# Felderblock_mini.net
KiCad netlist of a schematic drawn in EAGLE
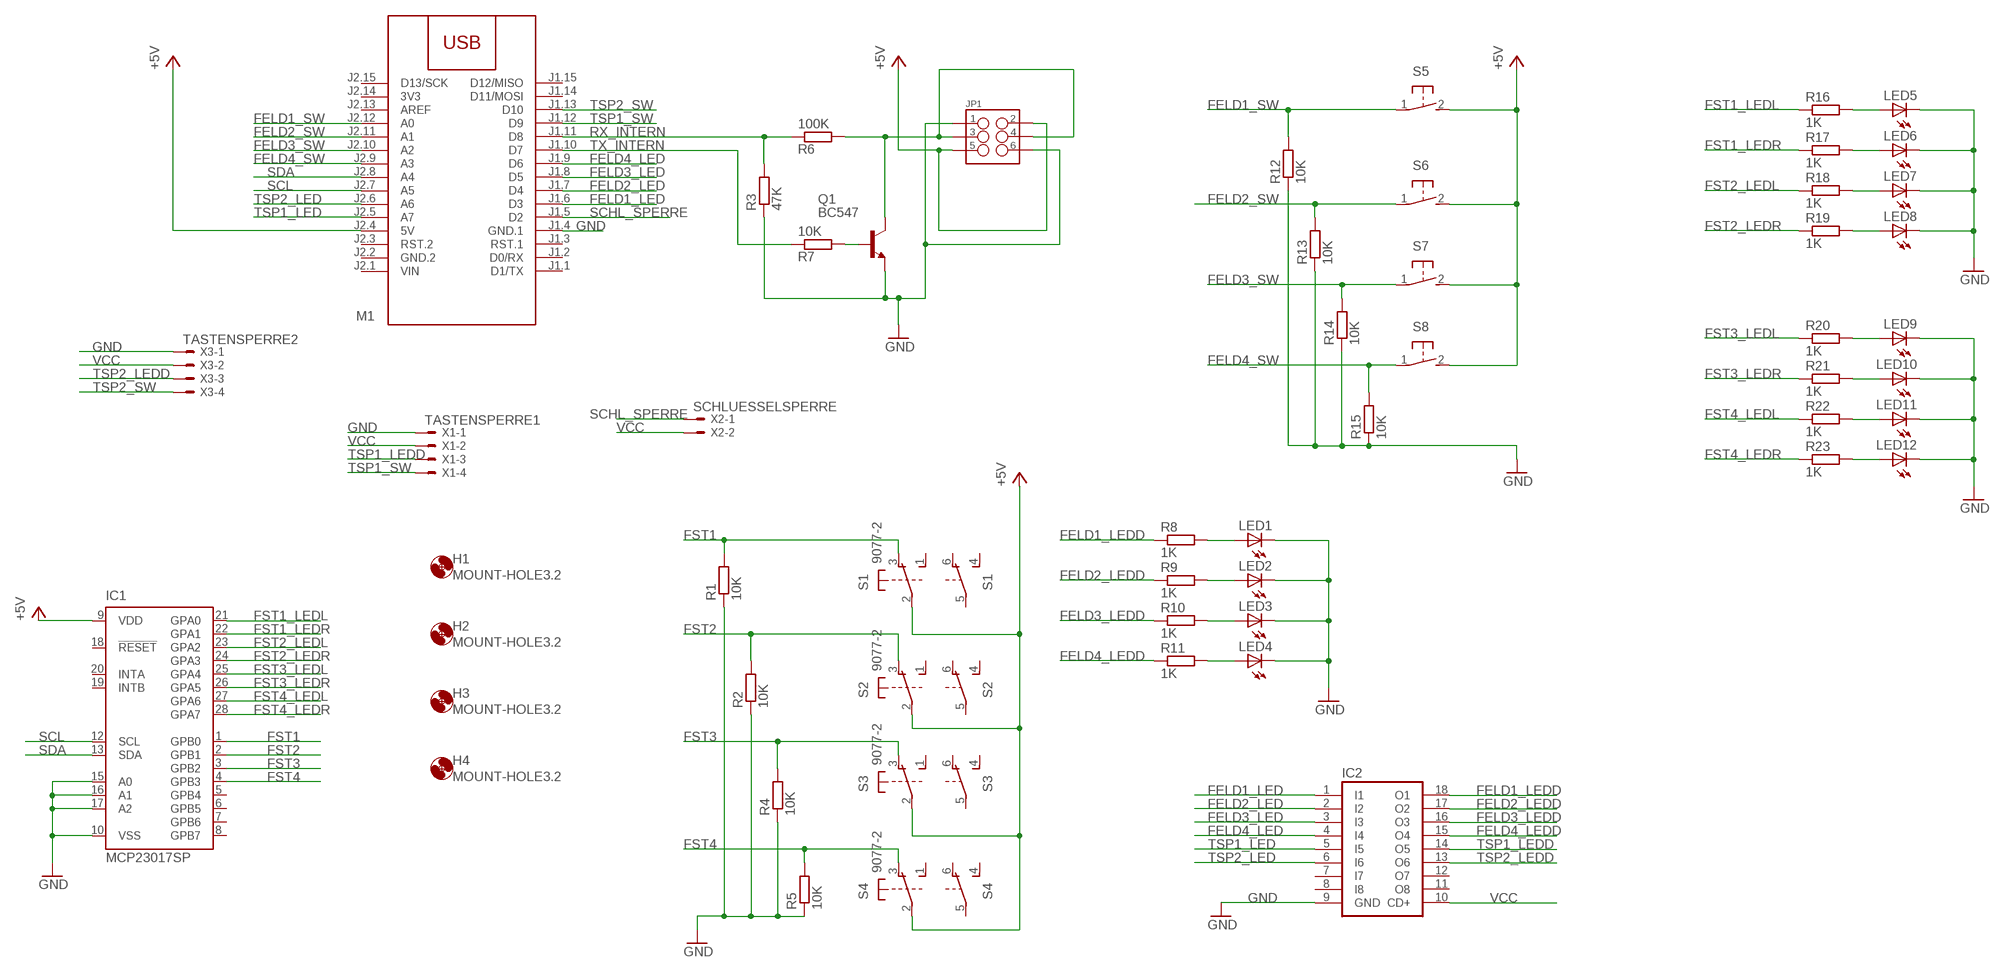
[diagram p0: schematic, sheet 1]

(export (version "E")
  (design (tool "Eeschema 10.0.6"))
  (components
    (comp (ref "H1")
      (value "MOUNT-HOLE3.2")
      (footprint "eagle-import:3,2")
      (libsource (lib "eagle-import") (part "MOUNT-HOLE3.2"))
    )
    (comp (ref "H2")
      (value "MOUNT-HOLE3.2")
      (footprint "eagle-import:3,2")
      (libsource (lib "eagle-import") (part "MOUNT-HOLE3.2"))
    )
    (comp (ref "H3")
      (value "MOUNT-HOLE3.2")
      (footprint "eagle-import:3,2")
      (libsource (lib "eagle-import") (part "MOUNT-HOLE3.2"))
    )
    (comp (ref "H4")
      (value "MOUNT-HOLE3.2")
      (footprint "eagle-import:3,2")
      (libsource (lib "eagle-import") (part "MOUNT-HOLE3.2"))
    )
    (comp (ref "IC1")
      (value "MCP23017SP")
      (footprint "eagle-import:DIL28-3")
      (fields (field (name "MF") "MICROCHIP") (field (name "MPN") "MCP23017-E/SP"))
      (libsource (lib "eagle-import") (part "MCP23017SP"))
    )
    (comp (ref "IC2")
      (value "ULN2803A")
      (footprint "eagle-import:DIL18")
      (libsource (lib "eagle-import") (part "ULN2803A"))
    )
    (comp (ref "JP1")
      (value "M03X2SHROUD")
      (footprint "eagle-import:2X3-SHROUDED")
      (libsource (lib "eagle-import") (part "M03X2SHROUD"))
    )
    (comp (ref "LED1")
      (value "LED10MM")
      (footprint "eagle-import:LED10MM")
      (libsource (lib "eagle-import") (part "LED10MM"))
    )
    (comp (ref "LED2")
      (value "LED10MM")
      (footprint "eagle-import:LED10MM")
      (libsource (lib "eagle-import") (part "LED10MM"))
    )
    (comp (ref "LED3")
      (value "LED10MM")
      (footprint "eagle-import:LED10MM")
      (libsource (lib "eagle-import") (part "LED10MM"))
    )
    (comp (ref "LED4")
      (value "LED10MM")
      (footprint "eagle-import:LED10MM")
      (libsource (lib "eagle-import") (part "LED10MM"))
    )
    (comp (ref "LED5")
      (value "LED5MM")
      (footprint "eagle-import:LED5MM")
      (libsource (lib "eagle-import") (part "LED5MM"))
    )
    (comp (ref "LED6")
      (value "LED5MM")
      (footprint "eagle-import:LED5MM")
      (libsource (lib "eagle-import") (part "LED5MM"))
    )
    (comp (ref "LED7")
      (value "LED5MM")
      (footprint "eagle-import:LED5MM")
      (libsource (lib "eagle-import") (part "LED5MM"))
    )
    (comp (ref "LED8")
      (value "LED5MM")
      (footprint "eagle-import:LED5MM")
      (libsource (lib "eagle-import") (part "LED5MM"))
    )
    (comp (ref "LED9")
      (value "LED5MM")
      (footprint "eagle-import:LED5MM")
      (libsource (lib "eagle-import") (part "LED5MM"))
    )
    (comp (ref "LED10")
      (value "LED5MM")
      (footprint "eagle-import:LED5MM")
      (libsource (lib "eagle-import") (part "LED5MM"))
    )
    (comp (ref "LED11")
      (value "LED5MM")
      (footprint "eagle-import:LED5MM")
      (libsource (lib "eagle-import") (part "LED5MM"))
    )
    (comp (ref "LED12")
      (value "LED5MM")
      (footprint "eagle-import:LED5MM")
      (libsource (lib "eagle-import") (part "LED5MM"))
    )
    (comp (ref "M1")
      (value "ARDUINO-NANO-3.0")
      (footprint "eagle-import:ARDUINO-NANO-3.0")
      (libsource (lib "eagle-import") (part "ARDUINO-NANO-3.0"))
    )
    (comp (ref "Q1")
      (value "BC547")
      (footprint "eagle-import:TO92")
      (libsource (lib "eagle-import") (part "BC547"))
    )
    (comp (ref "R1")
      (value "10K")
      (footprint "eagle-import:0207_7")
      (libsource (lib "eagle-import") (part "resistor_R-EU_0207/7"))
    )
    (comp (ref "R2")
      (value "10K")
      (footprint "eagle-import:0207_7")
      (libsource (lib "eagle-import") (part "resistor_R-EU_0207/7"))
    )
    (comp (ref "R3")
      (value "47K")
      (footprint "eagle-import:R1206")
      (libsource (lib "eagle-import") (part "R-EU_R1206"))
    )
    (comp (ref "R4")
      (value "10K")
      (footprint "eagle-import:0207_7")
      (libsource (lib "eagle-import") (part "resistor_R-EU_0207/7"))
    )
    (comp (ref "R5")
      (value "10K")
      (footprint "eagle-import:0207_7")
      (libsource (lib "eagle-import") (part "resistor_R-EU_0207/7"))
    )
    (comp (ref "R6")
      (value "100K")
      (footprint "eagle-import:R1206")
      (libsource (lib "eagle-import") (part "R-EU_R1206"))
    )
    (comp (ref "R7")
      (value "10K")
      (footprint "eagle-import:R1206")
      (libsource (lib "eagle-import") (part "R-EU_R1206"))
    )
    (comp (ref "R8")
      (value "1K")
      (footprint "eagle-import:0207_7")
      (libsource (lib "eagle-import") (part "resistor_R-EU_0207/7"))
    )
    (comp (ref "R9")
      (value "1K")
      (footprint "eagle-import:0207_7")
      (libsource (lib "eagle-import") (part "resistor_R-EU_0207/7"))
    )
    (comp (ref "R10")
      (value "1K")
      (footprint "eagle-import:0207_7")
      (libsource (lib "eagle-import") (part "resistor_R-EU_0207/7"))
    )
    (comp (ref "R11")
      (value "1K")
      (footprint "eagle-import:0207_7")
      (libsource (lib "eagle-import") (part "resistor_R-EU_0207/7"))
    )
    (comp (ref "R12")
      (value "10K")
      (footprint "eagle-import:0207_7")
      (libsource (lib "eagle-import") (part "resistor_R-EU_0207/7"))
    )
    (comp (ref "R13")
      (value "10K")
      (footprint "eagle-import:0207_7")
      (libsource (lib "eagle-import") (part "resistor_R-EU_0207/7"))
    )
    (comp (ref "R14")
      (value "10K")
      (footprint "eagle-import:0207_7")
      (libsource (lib "eagle-import") (part "resistor_R-EU_0207/7"))
    )
    (comp (ref "R15")
      (value "10K")
      (footprint "eagle-import:0207_7")
      (libsource (lib "eagle-import") (part "resistor_R-EU_0207/7"))
    )
    (comp (ref "R16")
      (value "1K")
      (footprint "eagle-import:0207_7")
      (libsource (lib "eagle-import") (part "resistor_R-EU_0207/7"))
    )
    (comp (ref "R17")
      (value "1K")
      (footprint "eagle-import:0207_7")
      (libsource (lib "eagle-import") (part "resistor_R-EU_0207/7"))
    )
    (comp (ref "R18")
      (value "1K")
      (footprint "eagle-import:0207_7")
      (libsource (lib "eagle-import") (part "resistor_R-EU_0207/7"))
    )
    (comp (ref "R19")
      (value "1K")
      (footprint "eagle-import:0207_7")
      (libsource (lib "eagle-import") (part "resistor_R-EU_0207/7"))
    )
    (comp (ref "R20")
      (value "1K")
      (footprint "eagle-import:0207_7")
      (libsource (lib "eagle-import") (part "resistor_R-EU_0207/7"))
    )
    (comp (ref "R21")
      (value "1K")
      (footprint "eagle-import:0207_7")
      (libsource (lib "eagle-import") (part "resistor_R-EU_0207/7"))
    )
    (comp (ref "R22")
      (value "1K")
      (footprint "eagle-import:0207_7")
      (libsource (lib "eagle-import") (part "resistor_R-EU_0207/7"))
    )
    (comp (ref "R23")
      (value "1K")
      (footprint "eagle-import:0207_7")
      (libsource (lib "eagle-import") (part "resistor_R-EU_0207/7"))
    )
    (comp (ref "S1")
      (value "9077-2")
      (footprint "eagle-import:9077-2")
      (libsource (lib "eagle-import") (part "9077-2"))
    )
    (comp (ref "S2")
      (value "9077-2")
      (footprint "eagle-import:9077-2")
      (libsource (lib "eagle-import") (part "9077-2"))
    )
    (comp (ref "S3")
      (value "9077-2")
      (footprint "eagle-import:9077-2")
      (libsource (lib "eagle-import") (part "9077-2"))
    )
    (comp (ref "S4")
      (value "9077-2")
      (footprint "eagle-import:9077-2")
      (libsource (lib "eagle-import") (part "9077-2"))
    )
    (comp (ref "S5")
      (value "31-XX")
      (footprint "eagle-import:B3F-31XX")
      (fields (field (name "MPN") "B3F-3100"))
      (libsource (lib "eagle-import") (part "31-XX"))
    )
    (comp (ref "S6")
      (value "31-XX")
      (footprint "eagle-import:B3F-31XX")
      (fields (field (name "MPN") "B3F-3100"))
      (libsource (lib "eagle-import") (part "31-XX"))
    )
    (comp (ref "S7")
      (value "31-XX")
      (footprint "eagle-import:B3F-31XX")
      (fields (field (name "MPN") "B3F-3100"))
      (libsource (lib "eagle-import") (part "31-XX"))
    )
    (comp (ref "S8")
      (value "31-XX")
      (footprint "eagle-import:B3F-31XX")
      (fields (field (name "MPN") "B3F-3100"))
      (libsource (lib "eagle-import") (part "31-XX"))
    )
    (comp (ref "X1")
      (value "TASTENSPERRE1")
      (footprint "eagle-import:22-23-2041")
      (fields (field (name "MF") "MOLEX") (field (name "MPN") "22-23-2041"))
      (libsource (lib "eagle-import") (part "22-23-2041"))
    )
    (comp (ref "X2")
      (value "SCHLUESSELSPERRE")
      (footprint "eagle-import:22-23-2021")
      (fields (field (name "MF") "MOLEX") (field (name "MPN") "22-23-2021"))
      (libsource (lib "eagle-import") (part "22-23-2021"))
    )
    (comp (ref "X3")
      (value "TASTENSPERRE2")
      (footprint "eagle-import:22-23-2041")
      (fields (field (name "MF") "MOLEX") (field (name "MPN") "22-23-2041"))
      (libsource (lib "eagle-import") (part "22-23-2041"))
    )
  )
  (nets
    (net (code "1") (name "+5V") (class "Default")
      (node (ref "IC1") (pin "9") (pinfunction "VDD_9") (pintype "power_in"))
      (node (ref "IC2") (pin "10") (pinfunction "CD+_10") (pintype "passive"))
      (node (ref "JP1") (pin "2") (pinfunction "2_2") (pintype "bidirectional"))
      (node (ref "JP1") (pin "5") (pinfunction "5_5") (pintype "bidirectional"))
      (node (ref "M1") (pin "J2.4") (pinfunction "5V_J2.4") (pintype "power_in"))
      (node (ref "S1") (pin "2") (pinfunction "P_2") (pintype "passive"))
      (node (ref "S2") (pin "2") (pinfunction "P_2") (pintype "passive"))
      (node (ref "S3") (pin "2") (pinfunction "P_2") (pintype "passive"))
      (node (ref "S4") (pin "2") (pinfunction "P_2") (pintype "passive"))
      (node (ref "S5") (pin "2") (pinfunction "S_2") (pintype "passive"))
      (node (ref "S6") (pin "2") (pinfunction "S_2") (pintype "passive"))
      (node (ref "S7") (pin "2") (pinfunction "S_2") (pintype "passive"))
      (node (ref "S8") (pin "2") (pinfunction "S_2") (pintype "passive"))
      (node (ref "X1") (pin "2") (pinfunction "S_2") (pintype "passive"))
      (node (ref "X2") (pin "2") (pinfunction "S_2") (pintype "passive"))
      (node (ref "X3") (pin "2") (pinfunction "S_2") (pintype "passive"))
    )
    (net (code "2") (name "/3V3") (class "Default")
      (node (ref "M1") (pin "J2.14") (pinfunction "3V3_J2.14") (pintype "power_in"))
    )
    (net (code "3") (name "/FELD1_LED") (class "Default")
      (node (ref "IC2") (pin "1") (pinfunction "I1_1") (pintype "input"))
      (node (ref "M1") (pin "J1.6") (pinfunction "D3_J1.6") (pintype "bidirectional"))
    )
    (net (code "4") (name "/FELD1_LEDD") (class "Default")
      (node (ref "IC2") (pin "18") (pinfunction "O1_18") (pintype "open_collector"))
      (node (ref "R8") (pin "1") (pinfunction "1_1") (pintype "passive"))
    )
    (net (code "5") (name "/FELD1_SW") (class "Default")
      (node (ref "M1") (pin "J2.12") (pinfunction "A0_J2.12") (pintype "bidirectional"))
      (node (ref "R12") (pin "2") (pinfunction "2_2") (pintype "passive"))
      (node (ref "S5") (pin "1") (pinfunction "P_1") (pintype "passive"))
    )
    (net (code "6") (name "/FELD2_LED") (class "Default")
      (node (ref "IC2") (pin "2") (pinfunction "I2_2") (pintype "input"))
      (node (ref "M1") (pin "J1.7") (pinfunction "D4_J1.7") (pintype "bidirectional"))
    )
    (net (code "7") (name "/FELD2_LEDD") (class "Default")
      (node (ref "IC2") (pin "17") (pinfunction "O2_17") (pintype "open_collector"))
      (node (ref "R9") (pin "1") (pinfunction "1_1") (pintype "passive"))
    )
    (net (code "8") (name "/FELD2_SW") (class "Default")
      (node (ref "M1") (pin "J2.11") (pinfunction "A1_J2.11") (pintype "bidirectional"))
      (node (ref "R13") (pin "2") (pinfunction "2_2") (pintype "passive"))
      (node (ref "S6") (pin "1") (pinfunction "P_1") (pintype "passive"))
    )
    (net (code "9") (name "/FELD3_LED") (class "Default")
      (node (ref "IC2") (pin "3") (pinfunction "I3_3") (pintype "input"))
      (node (ref "M1") (pin "J1.8") (pinfunction "D5_J1.8") (pintype "bidirectional"))
    )
    (net (code "10") (name "/FELD3_LEDD") (class "Default")
      (node (ref "IC2") (pin "16") (pinfunction "O3_16") (pintype "open_collector"))
      (node (ref "R10") (pin "1") (pinfunction "1_1") (pintype "passive"))
    )
    (net (code "11") (name "/FELD3_SW") (class "Default")
      (node (ref "M1") (pin "J2.10") (pinfunction "A2_J2.10") (pintype "bidirectional"))
      (node (ref "R14") (pin "2") (pinfunction "2_2") (pintype "passive"))
      (node (ref "S7") (pin "1") (pinfunction "P_1") (pintype "passive"))
    )
    (net (code "12") (name "/FELD4_LED") (class "Default")
      (node (ref "IC2") (pin "4") (pinfunction "I4_4") (pintype "input"))
      (node (ref "M1") (pin "J1.9") (pinfunction "D6_J1.9") (pintype "bidirectional"))
    )
    (net (code "13") (name "/FELD4_LEDD") (class "Default")
      (node (ref "IC2") (pin "15") (pinfunction "O4_15") (pintype "open_collector"))
      (node (ref "R11") (pin "1") (pinfunction "1_1") (pintype "passive"))
    )
    (net (code "14") (name "/FELD4_SW") (class "Default")
      (node (ref "M1") (pin "J2.9") (pinfunction "A3_J2.9") (pintype "bidirectional"))
      (node (ref "R15") (pin "2") (pinfunction "2_2") (pintype "passive"))
      (node (ref "S8") (pin "1") (pinfunction "P_1") (pintype "passive"))
    )
    (net (code "15") (name "/FST1") (class "Default")
      (node (ref "IC1") (pin "1") (pinfunction "GPB0_1") (pintype "bidirectional"))
      (node (ref "R1") (pin "2") (pinfunction "2_2") (pintype "passive"))
      (node (ref "S1") (pin "3") (pinfunction "O_3") (pintype "passive"))
    )
    (net (code "16") (name "/FST1_LEDL") (class "Default")
      (node (ref "IC1") (pin "21") (pinfunction "GPA0_21") (pintype "bidirectional"))
      (node (ref "R16") (pin "1") (pinfunction "1_1") (pintype "passive"))
    )
    (net (code "17") (name "/FST1_LEDR") (class "Default")
      (node (ref "IC1") (pin "22") (pinfunction "GPA1_22") (pintype "bidirectional"))
      (node (ref "R17") (pin "1") (pinfunction "1_1") (pintype "passive"))
    )
    (net (code "18") (name "/FST2") (class "Default")
      (node (ref "IC1") (pin "2") (pinfunction "GPB1_2") (pintype "bidirectional"))
      (node (ref "R2") (pin "2") (pinfunction "2_2") (pintype "passive"))
      (node (ref "S2") (pin "3") (pinfunction "O_3") (pintype "passive"))
    )
    (net (code "19") (name "/FST2_LEDL") (class "Default")
      (node (ref "IC1") (pin "23") (pinfunction "GPA2_23") (pintype "bidirectional"))
      (node (ref "R18") (pin "1") (pinfunction "1_1") (pintype "passive"))
    )
    (net (code "20") (name "/FST2_LEDR") (class "Default")
      (node (ref "IC1") (pin "24") (pinfunction "GPA3_24") (pintype "bidirectional"))
      (node (ref "R19") (pin "1") (pinfunction "1_1") (pintype "passive"))
    )
    (net (code "21") (name "/FST3") (class "Default")
      (node (ref "IC1") (pin "3") (pinfunction "GPB2_3") (pintype "bidirectional"))
      (node (ref "R4") (pin "2") (pinfunction "2_2") (pintype "passive"))
      (node (ref "S3") (pin "3") (pinfunction "O_3") (pintype "passive"))
    )
    (net (code "22") (name "/FST3_LEDL") (class "Default")
      (node (ref "IC1") (pin "25") (pinfunction "GPA4_25") (pintype "bidirectional"))
      (node (ref "R20") (pin "1") (pinfunction "1_1") (pintype "passive"))
    )
    (net (code "23") (name "/FST3_LEDR") (class "Default")
      (node (ref "IC1") (pin "26") (pinfunction "GPA5_26") (pintype "bidirectional"))
      (node (ref "R21") (pin "1") (pinfunction "1_1") (pintype "passive"))
    )
    (net (code "24") (name "/FST4") (class "Default")
      (node (ref "IC1") (pin "4") (pinfunction "GPB3_4") (pintype "bidirectional"))
      (node (ref "R5") (pin "2") (pinfunction "2_2") (pintype "passive"))
      (node (ref "S4") (pin "3") (pinfunction "O_3") (pintype "passive"))
    )
    (net (code "25") (name "/FST4_LEDL") (class "Default")
      (node (ref "IC1") (pin "27") (pinfunction "GPA6_27") (pintype "bidirectional"))
      (node (ref "R22") (pin "1") (pinfunction "1_1") (pintype "passive"))
    )
    (net (code "26") (name "/FST4_LEDR") (class "Default")
      (node (ref "IC1") (pin "28") (pinfunction "GPA7_28") (pintype "bidirectional"))
      (node (ref "R23") (pin "1") (pinfunction "1_1") (pintype "passive"))
    )
    (net (code "27") (name "/GND.2") (class "Default")
      (node (ref "M1") (pin "J2.2") (pinfunction "GND.2_J2.2") (pintype "power_in"))
    )
    (net (code "28") (name "/RX_INTERN") (class "Default")
      (node (ref "M1") (pin "J1.11") (pinfunction "D8_J1.11") (pintype "bidirectional"))
      (node (ref "R3") (pin "2") (pinfunction "2_2") (pintype "passive"))
      (node (ref "R6") (pin "1") (pinfunction "1_1") (pintype "passive"))
    )
    (net (code "29") (name "/SCHL_SPERRE") (class "Default")
      (node (ref "M1") (pin "J1.5") (pinfunction "D2_J1.5") (pintype "bidirectional"))
      (node (ref "X2") (pin "1") (pinfunction "S_1") (pintype "passive"))
    )
    (net (code "30") (name "/SCL") (class "Default")
      (node (ref "IC1") (pin "12") (pinfunction "SCL_12") (pintype "input"))
      (node (ref "M1") (pin "J2.7") (pinfunction "A5_J2.7") (pintype "bidirectional"))
    )
    (net (code "31") (name "/SDA") (class "Default")
      (node (ref "IC1") (pin "13") (pinfunction "SDA_13") (pintype "bidirectional"))
      (node (ref "M1") (pin "J2.8") (pinfunction "A4_J2.8") (pintype "bidirectional"))
    )
    (net (code "32") (name "/TSP1_LED") (class "Default")
      (node (ref "IC2") (pin "5") (pinfunction "I5_5") (pintype "input"))
      (node (ref "M1") (pin "J2.5") (pinfunction "A7_J2.5") (pintype "bidirectional"))
    )
    (net (code "33") (name "/TSP1_LEDD") (class "Default")
      (node (ref "IC2") (pin "14") (pinfunction "O5_14") (pintype "open_collector"))
      (node (ref "X1") (pin "3") (pinfunction "S_3") (pintype "passive"))
    )
    (net (code "34") (name "/TSP1_SW") (class "Default")
      (node (ref "M1") (pin "J1.12") (pinfunction "D9_J1.12") (pintype "bidirectional"))
      (node (ref "X1") (pin "4") (pinfunction "S_4") (pintype "passive"))
    )
    (net (code "35") (name "/TSP2_LED") (class "Default")
      (node (ref "IC2") (pin "6") (pinfunction "I6_6") (pintype "input"))
      (node (ref "M1") (pin "J2.6") (pinfunction "A6_J2.6") (pintype "bidirectional"))
    )
    (net (code "36") (name "/TSP2_LEDD") (class "Default")
      (node (ref "IC2") (pin "13") (pinfunction "O6_13") (pintype "open_collector"))
      (node (ref "X3") (pin "3") (pinfunction "S_3") (pintype "passive"))
    )
    (net (code "37") (name "/TSP2_SW") (class "Default")
      (node (ref "M1") (pin "J1.13") (pinfunction "D10_J1.13") (pintype "bidirectional"))
      (node (ref "X3") (pin "4") (pinfunction "S_4") (pintype "passive"))
    )
    (net (code "38") (name "/TX_INTERN") (class "Default")
      (node (ref "M1") (pin "J1.10") (pinfunction "D7_J1.10") (pintype "bidirectional"))
      (node (ref "R7") (pin "1") (pinfunction "1_1") (pintype "passive"))
    )
    (net (code "39") (name "/VIN") (class "Default")
      (node (ref "M1") (pin "J2.1") (pinfunction "VIN_J2.1") (pintype "power_in"))
    )
    (net (code "40") (name "GND") (class "Default")
      (node (ref "IC1") (pin "10") (pinfunction "VSS_10") (pintype "power_in"))
      (node (ref "IC1") (pin "15") (pinfunction "A0_15") (pintype "input"))
      (node (ref "IC1") (pin "16") (pinfunction "A1_16") (pintype "input"))
      (node (ref "IC1") (pin "17") (pinfunction "A2_17") (pintype "input"))
      (node (ref "IC2") (pin "9") (pinfunction "GND_9") (pintype "power_in"))
      (node (ref "JP1") (pin "1") (pinfunction "1_1") (pintype "bidirectional"))
      (node (ref "JP1") (pin "6") (pinfunction "6_6") (pintype "bidirectional"))
      (node (ref "LED1") (pin "C") (pinfunction "C_C") (pintype "passive"))
      (node (ref "LED10") (pin "K") (pinfunction "C_K") (pintype "passive"))
      (node (ref "LED11") (pin "K") (pinfunction "C_K") (pintype "passive"))
      (node (ref "LED12") (pin "K") (pinfunction "C_K") (pintype "passive"))
      (node (ref "LED2") (pin "C") (pinfunction "C_C") (pintype "passive"))
      (node (ref "LED3") (pin "C") (pinfunction "C_C") (pintype "passive"))
      (node (ref "LED4") (pin "C") (pinfunction "C_C") (pintype "passive"))
      (node (ref "LED5") (pin "K") (pinfunction "C_K") (pintype "passive"))
      (node (ref "LED6") (pin "K") (pinfunction "C_K") (pintype "passive"))
      (node (ref "LED7") (pin "K") (pinfunction "C_K") (pintype "passive"))
      (node (ref "LED8") (pin "K") (pinfunction "C_K") (pintype "passive"))
      (node (ref "LED9") (pin "K") (pinfunction "C_K") (pintype "passive"))
      (node (ref "M1") (pin "J1.4") (pinfunction "GND.1_J1.4") (pintype "power_in"))
      (node (ref "Q1") (pin "1") (pinfunction "E_1") (pintype "passive"))
      (node (ref "R1") (pin "1") (pinfunction "1_1") (pintype "passive"))
      (node (ref "R12") (pin "1") (pinfunction "1_1") (pintype "passive"))
      (node (ref "R13") (pin "1") (pinfunction "1_1") (pintype "passive"))
      (node (ref "R14") (pin "1") (pinfunction "1_1") (pintype "passive"))
      (node (ref "R15") (pin "1") (pinfunction "1_1") (pintype "passive"))
      (node (ref "R2") (pin "1") (pinfunction "1_1") (pintype "passive"))
      (node (ref "R3") (pin "1") (pinfunction "1_1") (pintype "passive"))
      (node (ref "R4") (pin "1") (pinfunction "1_1") (pintype "passive"))
      (node (ref "R5") (pin "1") (pinfunction "1_1") (pintype "passive"))
      (node (ref "X1") (pin "1") (pinfunction "S_1") (pintype "passive"))
      (node (ref "X3") (pin "1") (pinfunction "S_1") (pintype "passive"))
    )
    (net (code "41") (name "Net-(LED1-PadA)") (class "Default")
      (node (ref "LED1") (pin "A") (pinfunction "A_A") (pintype "passive"))
      (node (ref "R8") (pin "2") (pinfunction "2_2") (pintype "passive"))
    )
    (net (code "42") (name "Net-(LED2-PadA)") (class "Default")
      (node (ref "LED2") (pin "A") (pinfunction "A_A") (pintype "passive"))
      (node (ref "R9") (pin "2") (pinfunction "2_2") (pintype "passive"))
    )
    (net (code "43") (name "Net-(LED3-PadA)") (class "Default")
      (node (ref "LED3") (pin "A") (pinfunction "A_A") (pintype "passive"))
      (node (ref "R10") (pin "2") (pinfunction "2_2") (pintype "passive"))
    )
    (net (code "44") (name "Net-(LED4-PadA)") (class "Default")
      (node (ref "LED4") (pin "A") (pinfunction "A_A") (pintype "passive"))
      (node (ref "R11") (pin "2") (pinfunction "2_2") (pintype "passive"))
    )
    (net (code "45") (name "Net-(LED5-PadA)") (class "Default")
      (node (ref "LED5") (pin "A") (pinfunction "A_A") (pintype "passive"))
      (node (ref "R16") (pin "2") (pinfunction "2_2") (pintype "passive"))
    )
    (net (code "46") (name "Net-(LED6-PadA)") (class "Default")
      (node (ref "LED6") (pin "A") (pinfunction "A_A") (pintype "passive"))
      (node (ref "R17") (pin "2") (pinfunction "2_2") (pintype "passive"))
    )
    (net (code "47") (name "Net-(LED7-PadA)") (class "Default")
      (node (ref "LED7") (pin "A") (pinfunction "A_A") (pintype "passive"))
      (node (ref "R18") (pin "2") (pinfunction "2_2") (pintype "passive"))
    )
    (net (code "48") (name "Net-(LED8-PadA)") (class "Default")
      (node (ref "LED8") (pin "A") (pinfunction "A_A") (pintype "passive"))
      (node (ref "R19") (pin "2") (pinfunction "2_2") (pintype "passive"))
    )
    (net (code "49") (name "Net-(LED9-PadA)") (class "Default")
      (node (ref "LED9") (pin "A") (pinfunction "A_A") (pintype "passive"))
      (node (ref "R20") (pin "2") (pinfunction "2_2") (pintype "passive"))
    )
    (net (code "50") (name "Net-(LED10-PadA)") (class "Default")
      (node (ref "LED10") (pin "A") (pinfunction "A_A") (pintype "passive"))
      (node (ref "R21") (pin "2") (pinfunction "2_2") (pintype "passive"))
    )
    (net (code "51") (name "Net-(LED11-PadA)") (class "Default")
      (node (ref "LED11") (pin "A") (pinfunction "A_A") (pintype "passive"))
      (node (ref "R22") (pin "2") (pinfunction "2_2") (pintype "passive"))
    )
    (net (code "52") (name "Net-(LED12-PadA)") (class "Default")
      (node (ref "LED12") (pin "A") (pinfunction "A_A") (pintype "passive"))
      (node (ref "R23") (pin "2") (pinfunction "2_2") (pintype "passive"))
    )
    (net (code "53") (name "Net-(Q1-B)") (class "Default")
      (node (ref "Q1") (pin "2") (pinfunction "B_2") (pintype "passive"))
      (node (ref "R7") (pin "2") (pinfunction "2_2") (pintype "passive"))
    )
    (net (code "54") (name "Net-(Q1-C)") (class "Default")
      (node (ref "JP1") (pin "3") (pinfunction "3_3") (pintype "bidirectional"))
      (node (ref "JP1") (pin "4") (pinfunction "4_4") (pintype "bidirectional"))
      (node (ref "Q1") (pin "3") (pinfunction "C_3") (pintype "passive"))
      (node (ref "R6") (pin "2") (pinfunction "2_2") (pintype "passive"))
    )
    (net (code "55") (name "unconnected-(IC1-GPB4-Pad5)") (class "Default")
      (node (ref "IC1") (pin "5") (pinfunction "GPB4_5") (pintype "bidirectional"))
    )
    (net (code "56") (name "unconnected-(IC1-GPB5-Pad6)") (class "Default")
      (node (ref "IC1") (pin "6") (pinfunction "GPB5_6") (pintype "bidirectional"))
    )
    (net (code "57") (name "unconnected-(IC1-GPB6-Pad7)") (class "Default")
      (node (ref "IC1") (pin "7") (pinfunction "GPB6_7") (pintype "bidirectional"))
    )
    (net (code "58") (name "unconnected-(IC1-GPB7-Pad8)") (class "Default")
      (node (ref "IC1") (pin "8") (pinfunction "GPB7_8") (pintype "bidirectional"))
    )
    (net (code "59") (name "unconnected-(IC1-INTA-Pad20)") (class "Default")
      (node (ref "IC1") (pin "20") (pinfunction "INTA_20") (pintype "output"))
    )
    (net (code "60") (name "unconnected-(IC1-INTB-Pad19)") (class "Default")
      (node (ref "IC1") (pin "19") (pinfunction "INTB_19") (pintype "output"))
    )
    (net (code "61") (name "unconnected-(IC1-~{RESET}-Pad18)") (class "Default")
      (node (ref "IC1") (pin "18") (pinfunction "~{RESET}_18") (pintype "input"))
    )
    (net (code "62") (name "unconnected-(IC2-I7-Pad7)") (class "Default")
      (node (ref "IC2") (pin "7") (pinfunction "I7_7") (pintype "input"))
    )
    (net (code "63") (name "unconnected-(IC2-I8-Pad8)") (class "Default")
      (node (ref "IC2") (pin "8") (pinfunction "I8_8") (pintype "input"))
    )
    (net (code "64") (name "unconnected-(IC2-O7-Pad12)") (class "Default")
      (node (ref "IC2") (pin "12") (pinfunction "O7_12") (pintype "open_collector"))
    )
    (net (code "65") (name "unconnected-(IC2-O8-Pad11)") (class "Default")
      (node (ref "IC2") (pin "11") (pinfunction "O8_11") (pintype "open_collector"))
    )
    (net (code "66") (name "unconnected-(M1-AREF-PadJ2.13)") (class "Default")
      (node (ref "M1") (pin "J2.13") (pinfunction "AREF_J2.13") (pintype "bidirectional"))
    )
    (net (code "67") (name "unconnected-(M1-D0{slash}RX-PadJ1.2)") (class "Default")
      (node (ref "M1") (pin "J1.2") (pinfunction "D0/RX_J1.2") (pintype "bidirectional"))
    )
    (net (code "68") (name "unconnected-(M1-D1{slash}TX-PadJ1.1)") (class "Default")
      (node (ref "M1") (pin "J1.1") (pinfunction "D1/TX_J1.1") (pintype "bidirectional"))
    )
    (net (code "69") (name "unconnected-(M1-D11{slash}MOSI-PadJ1.14)") (class "Default")
      (node (ref "M1") (pin "J1.14") (pinfunction "D11/MOSI_J1.14") (pintype "bidirectional"))
    )
    (net (code "70") (name "unconnected-(M1-D12{slash}MISO-PadJ1.15)") (class "Default")
      (node (ref "M1") (pin "J1.15") (pinfunction "D12/MISO_J1.15") (pintype "bidirectional"))
    )
    (net (code "71") (name "unconnected-(M1-D13{slash}SCK-PadJ2.15)") (class "Default")
      (node (ref "M1") (pin "J2.15") (pinfunction "D13/SCK_J2.15") (pintype "bidirectional"))
    )
    (net (code "72") (name "unconnected-(M1-RST.1-PadJ1.3)") (class "Default")
      (node (ref "M1") (pin "J1.3") (pinfunction "RST.1_J1.3") (pintype "bidirectional"))
    )
    (net (code "73") (name "unconnected-(M1-RST.2-PadJ2.3)") (class "Default")
      (node (ref "M1") (pin "J2.3") (pinfunction "RST.2_J2.3") (pintype "bidirectional"))
    )
    (net (code "74") (name "unconnected-(S1A-S-Pad1)") (class "Default")
      (node (ref "S1") (pin "1") (pinfunction "S_1") (pintype "passive"))
    )
    (net (code "75") (name "unconnected-(S1B-O-Pad6)") (class "Default")
      (node (ref "S1") (pin "6") (pinfunction "O_6") (pintype "passive"))
    )
    (net (code "76") (name "unconnected-(S1B-P-Pad5)") (class "Default")
      (node (ref "S1") (pin "5") (pinfunction "P_5") (pintype "passive"))
    )
    (net (code "77") (name "unconnected-(S1B-S-Pad4)") (class "Default")
      (node (ref "S1") (pin "4") (pinfunction "S_4") (pintype "passive"))
    )
    (net (code "78") (name "unconnected-(S2A-S-Pad1)") (class "Default")
      (node (ref "S2") (pin "1") (pinfunction "S_1") (pintype "passive"))
    )
    (net (code "79") (name "unconnected-(S2B-O-Pad6)") (class "Default")
      (node (ref "S2") (pin "6") (pinfunction "O_6") (pintype "passive"))
    )
    (net (code "80") (name "unconnected-(S2B-P-Pad5)") (class "Default")
      (node (ref "S2") (pin "5") (pinfunction "P_5") (pintype "passive"))
    )
    (net (code "81") (name "unconnected-(S2B-S-Pad4)") (class "Default")
      (node (ref "S2") (pin "4") (pinfunction "S_4") (pintype "passive"))
    )
    (net (code "82") (name "unconnected-(S3A-S-Pad1)") (class "Default")
      (node (ref "S3") (pin "1") (pinfunction "S_1") (pintype "passive"))
    )
    (net (code "83") (name "unconnected-(S3B-O-Pad6)") (class "Default")
      (node (ref "S3") (pin "6") (pinfunction "O_6") (pintype "passive"))
    )
    (net (code "84") (name "unconnected-(S3B-P-Pad5)") (class "Default")
      (node (ref "S3") (pin "5") (pinfunction "P_5") (pintype "passive"))
    )
    (net (code "85") (name "unconnected-(S3B-S-Pad4)") (class "Default")
      (node (ref "S3") (pin "4") (pinfunction "S_4") (pintype "passive"))
    )
    (net (code "86") (name "unconnected-(S4A-S-Pad1)") (class "Default")
      (node (ref "S4") (pin "1") (pinfunction "S_1") (pintype "passive"))
    )
    (net (code "87") (name "unconnected-(S4B-O-Pad6)") (class "Default")
      (node (ref "S4") (pin "6") (pinfunction "O_6") (pintype "passive"))
    )
    (net (code "88") (name "unconnected-(S4B-P-Pad5)") (class "Default")
      (node (ref "S4") (pin "5") (pinfunction "P_5") (pintype "passive"))
    )
    (net (code "89") (name "unconnected-(S4B-S-Pad4)") (class "Default")
      (node (ref "S4") (pin "4") (pinfunction "S_4") (pintype "passive"))
    )
  )
)
